# milhub.net
KiCad netlist of a schematic drawn in EAGLE
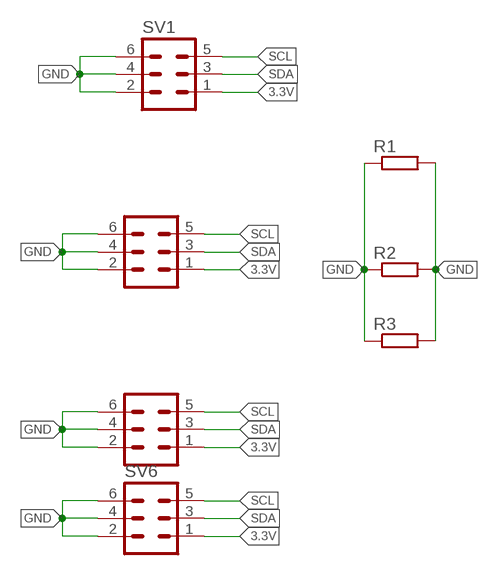
[diagram p0: schematic, sheet 1]

(export (version "E")
  (design (tool "Eeschema 10.0.6"))
  (components
    (comp (ref "R1")
      (value "R-EU_0207/10")
      (footprint "eagle-import:0207_10")
      (libsource (lib "eagle-import") (part "R-EU_0207/10"))
    )
    (comp (ref "R2")
      (value "R-EU_0207/10")
      (footprint "eagle-import:0207_10")
      (libsource (lib "eagle-import") (part "R-EU_0207/10"))
    )
    (comp (ref "R3")
      (value "R-EU_0207/10")
      (footprint "eagle-import:0207_10")
      (libsource (lib "eagle-import") (part "R-EU_0207/10"))
    )
    (comp (ref "SV1")
      (value "ML6")
      (footprint "eagle-import:ML6")
      (libsource (lib "eagle-import") (part "ML6"))
    )
    (comp (ref "SV3")
      (value "ML6")
      (footprint "eagle-import:ML6")
      (libsource (lib "eagle-import") (part "ML6"))
    )
    (comp (ref "SV5")
      (value "ML6")
      (footprint "eagle-import:ML6")
      (libsource (lib "eagle-import") (part "ML6"))
    )
    (comp (ref "SV6")
      (value "ML6")
      (footprint "eagle-import:ML6")
      (libsource (lib "eagle-import") (part "ML6"))
    )
  )
  (nets
    (net (code "1") (name "3.3V") (class "Default")
      (node (ref "SV1") (pin "1") (pinfunction "1_1") (pintype "passive"))
      (node (ref "SV3") (pin "1") (pinfunction "1_1") (pintype "passive"))
      (node (ref "SV5") (pin "1") (pinfunction "1_1") (pintype "passive"))
      (node (ref "SV6") (pin "1") (pinfunction "1_1") (pintype "passive"))
    )
    (net (code "2") (name "GND") (class "Default")
      (node (ref "R1") (pin "1") (pinfunction "1_1") (pintype "passive"))
      (node (ref "R1") (pin "2") (pinfunction "2_2") (pintype "passive"))
      (node (ref "R2") (pin "1") (pinfunction "1_1") (pintype "passive"))
      (node (ref "R2") (pin "2") (pinfunction "2_2") (pintype "passive"))
      (node (ref "R3") (pin "1") (pinfunction "1_1") (pintype "passive"))
      (node (ref "R3") (pin "2") (pinfunction "2_2") (pintype "passive"))
      (node (ref "SV1") (pin "2") (pinfunction "2_2") (pintype "passive"))
      (node (ref "SV1") (pin "4") (pinfunction "4_4") (pintype "passive"))
      (node (ref "SV1") (pin "6") (pinfunction "6_6") (pintype "passive"))
      (node (ref "SV3") (pin "2") (pinfunction "2_2") (pintype "passive"))
      (node (ref "SV3") (pin "4") (pinfunction "4_4") (pintype "passive"))
      (node (ref "SV3") (pin "6") (pinfunction "6_6") (pintype "passive"))
      (node (ref "SV5") (pin "2") (pinfunction "2_2") (pintype "passive"))
      (node (ref "SV5") (pin "4") (pinfunction "4_4") (pintype "passive"))
      (node (ref "SV5") (pin "6") (pinfunction "6_6") (pintype "passive"))
      (node (ref "SV6") (pin "2") (pinfunction "2_2") (pintype "passive"))
      (node (ref "SV6") (pin "4") (pinfunction "4_4") (pintype "passive"))
      (node (ref "SV6") (pin "6") (pinfunction "6_6") (pintype "passive"))
    )
    (net (code "3") (name "SCL") (class "Default")
      (node (ref "SV1") (pin "5") (pinfunction "5_5") (pintype "passive"))
      (node (ref "SV3") (pin "5") (pinfunction "5_5") (pintype "passive"))
      (node (ref "SV5") (pin "5") (pinfunction "5_5") (pintype "passive"))
      (node (ref "SV6") (pin "5") (pinfunction "5_5") (pintype "passive"))
    )
    (net (code "4") (name "SDA") (class "Default")
      (node (ref "SV1") (pin "3") (pinfunction "3_3") (pintype "passive"))
      (node (ref "SV3") (pin "3") (pinfunction "3_3") (pintype "passive"))
      (node (ref "SV5") (pin "3") (pinfunction "3_3") (pintype "passive"))
      (node (ref "SV6") (pin "3") (pinfunction "3_3") (pintype "passive"))
    )
  )
)
